# Sheet1.net
KiCad netlist of a schematic drawn in Altium Designer
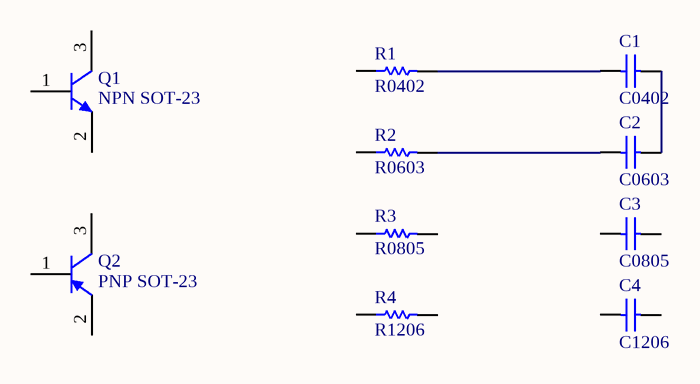
[diagram p0: Sheet1.SchDoc]

(export (version "E")
  (design (tool "Eeschema 10.0.6"))
  (components
    (comp (ref "C1")
      (value "C0402")
      (footprint "CAPC1005X06N")
      (description "Generic capacitor C0402")
      (libsource (lib "HW Git Lib") (part "NP-Capacitor"))
    )
    (comp (ref "C2")
      (value "C0603")
      (footprint "CAPC1608X09N")
      (description "Generic capacitor C0603")
      (libsource (lib "HW Git Lib") (part "NP-Capacitor"))
    )
    (comp (ref "C3")
      (value "C0805")
      (footprint "CAPC2012X12N")
      (description "Generic capacitor C0805")
      (libsource (lib "HW Git Lib") (part "NP-Capacitor"))
    )
    (comp (ref "C4")
      (value "C1206")
      (footprint "CAPC3216X19N")
      (description "Generic capacitor C1206")
      (libsource (lib "HW Git Lib") (part "NP-Capacitor"))
    )
    (comp (ref "Q1")
      (value "NPN SOT-23")
      (footprint "SOT95P245X110-3N")
      (description "Generic NPN BJT transistor SOT-23")
      (libsource (lib "HW Git Lib") (part "BJT-NPN-B1C3E2"))
    )
    (comp (ref "Q2")
      (value "PNP SOT-23")
      (footprint "SOT95P245X110-3N")
      (description "Generic PNP BJT transistor SOT-23")
      (libsource (lib "HW Git Lib") (part "BJT-PNP-B1C3E2"))
    )
    (comp (ref "R1")
      (value "R0402")
      (footprint "RESC1005X04N")
      (description "Generic resistor R0402")
      (libsource (lib "HW Git Lib") (part "Resistor"))
    )
    (comp (ref "R2")
      (value "R0603")
      (footprint "RESC1608X06N")
      (description "Generic resistor R0603")
      (libsource (lib "HW Git Lib") (part "Resistor"))
    )
    (comp (ref "R3")
      (value "R0805")
      (footprint "RESC2012X06N")
      (description "Generic resistor R0805")
      (libsource (lib "HW Git Lib") (part "Resistor"))
    )
    (comp (ref "R4")
      (value "R1206")
      (footprint "RESC3016X06N")
      (description "Generic resistor R1206")
      (libsource (lib "HW Git Lib") (part "Resistor"))
    )
  )
  (nets
    (net (code "1") (name "Net-(C1-Pad1)") (class "Default")
      (node (ref "C1") (pin "1") (pinfunction "1_1") (pintype "passive"))
      (node (ref "R1") (pin "2") (pinfunction "2_2") (pintype "passive"))
    )
    (net (code "2") (name "Net-(C1-Pad2)") (class "Default")
      (node (ref "C1") (pin "2") (pinfunction "2_2") (pintype "passive"))
      (node (ref "C2") (pin "2") (pinfunction "2_2") (pintype "passive"))
    )
    (net (code "3") (name "Net-(C2-Pad1)") (class "Default")
      (node (ref "C2") (pin "1") (pinfunction "1_1") (pintype "passive"))
      (node (ref "R2") (pin "2") (pinfunction "2_2") (pintype "passive"))
    )
    (net (code "4") (name "unconnected-(C3-Pad1)") (class "Default")
      (node (ref "C3") (pin "1") (pinfunction "1_1") (pintype "passive"))
    )
    (net (code "5") (name "unconnected-(C3-Pad2)") (class "Default")
      (node (ref "C3") (pin "2") (pinfunction "2_2") (pintype "passive"))
    )
    (net (code "6") (name "unconnected-(C4-Pad1)") (class "Default")
      (node (ref "C4") (pin "1") (pinfunction "1_1") (pintype "passive"))
    )
    (net (code "7") (name "unconnected-(C4-Pad2)") (class "Default")
      (node (ref "C4") (pin "2") (pinfunction "2_2") (pintype "passive"))
    )
    (net (code "8") (name "unconnected-(Q1-B-Pad1)") (class "Default")
      (node (ref "Q1") (pin "1") (pinfunction "B_1") (pintype "passive"))
    )
    (net (code "9") (name "unconnected-(Q1-C-Pad3)") (class "Default")
      (node (ref "Q1") (pin "3") (pinfunction "C_3") (pintype "passive"))
    )
    (net (code "10") (name "unconnected-(Q1-E-Pad2)") (class "Default")
      (node (ref "Q1") (pin "2") (pinfunction "E_2") (pintype "passive"))
    )
    (net (code "11") (name "unconnected-(Q2-B-Pad1)") (class "Default")
      (node (ref "Q2") (pin "1") (pinfunction "B_1") (pintype "passive"))
    )
    (net (code "12") (name "unconnected-(Q2-C-Pad3)") (class "Default")
      (node (ref "Q2") (pin "3") (pinfunction "C_3") (pintype "passive"))
    )
    (net (code "13") (name "unconnected-(Q2-E-Pad2)") (class "Default")
      (node (ref "Q2") (pin "2") (pinfunction "E_2") (pintype "passive"))
    )
    (net (code "14") (name "unconnected-(R1-Pad1)") (class "Default")
      (node (ref "R1") (pin "1") (pinfunction "1_1") (pintype "passive"))
    )
    (net (code "15") (name "unconnected-(R2-Pad1)") (class "Default")
      (node (ref "R2") (pin "1") (pinfunction "1_1") (pintype "passive"))
    )
    (net (code "16") (name "unconnected-(R3-Pad1)") (class "Default")
      (node (ref "R3") (pin "1") (pinfunction "1_1") (pintype "passive"))
    )
    (net (code "17") (name "unconnected-(R3-Pad2)") (class "Default")
      (node (ref "R3") (pin "2") (pinfunction "2_2") (pintype "passive"))
    )
    (net (code "18") (name "unconnected-(R4-Pad1)") (class "Default")
      (node (ref "R4") (pin "1") (pinfunction "1_1") (pintype "passive"))
    )
    (net (code "19") (name "unconnected-(R4-Pad2)") (class "Default")
      (node (ref "R4") (pin "2") (pinfunction "2_2") (pintype "passive"))
    )
  )
)
